# SCH_GD32_KB.net
KiCad netlist of a schematic drawn in EasyEDA
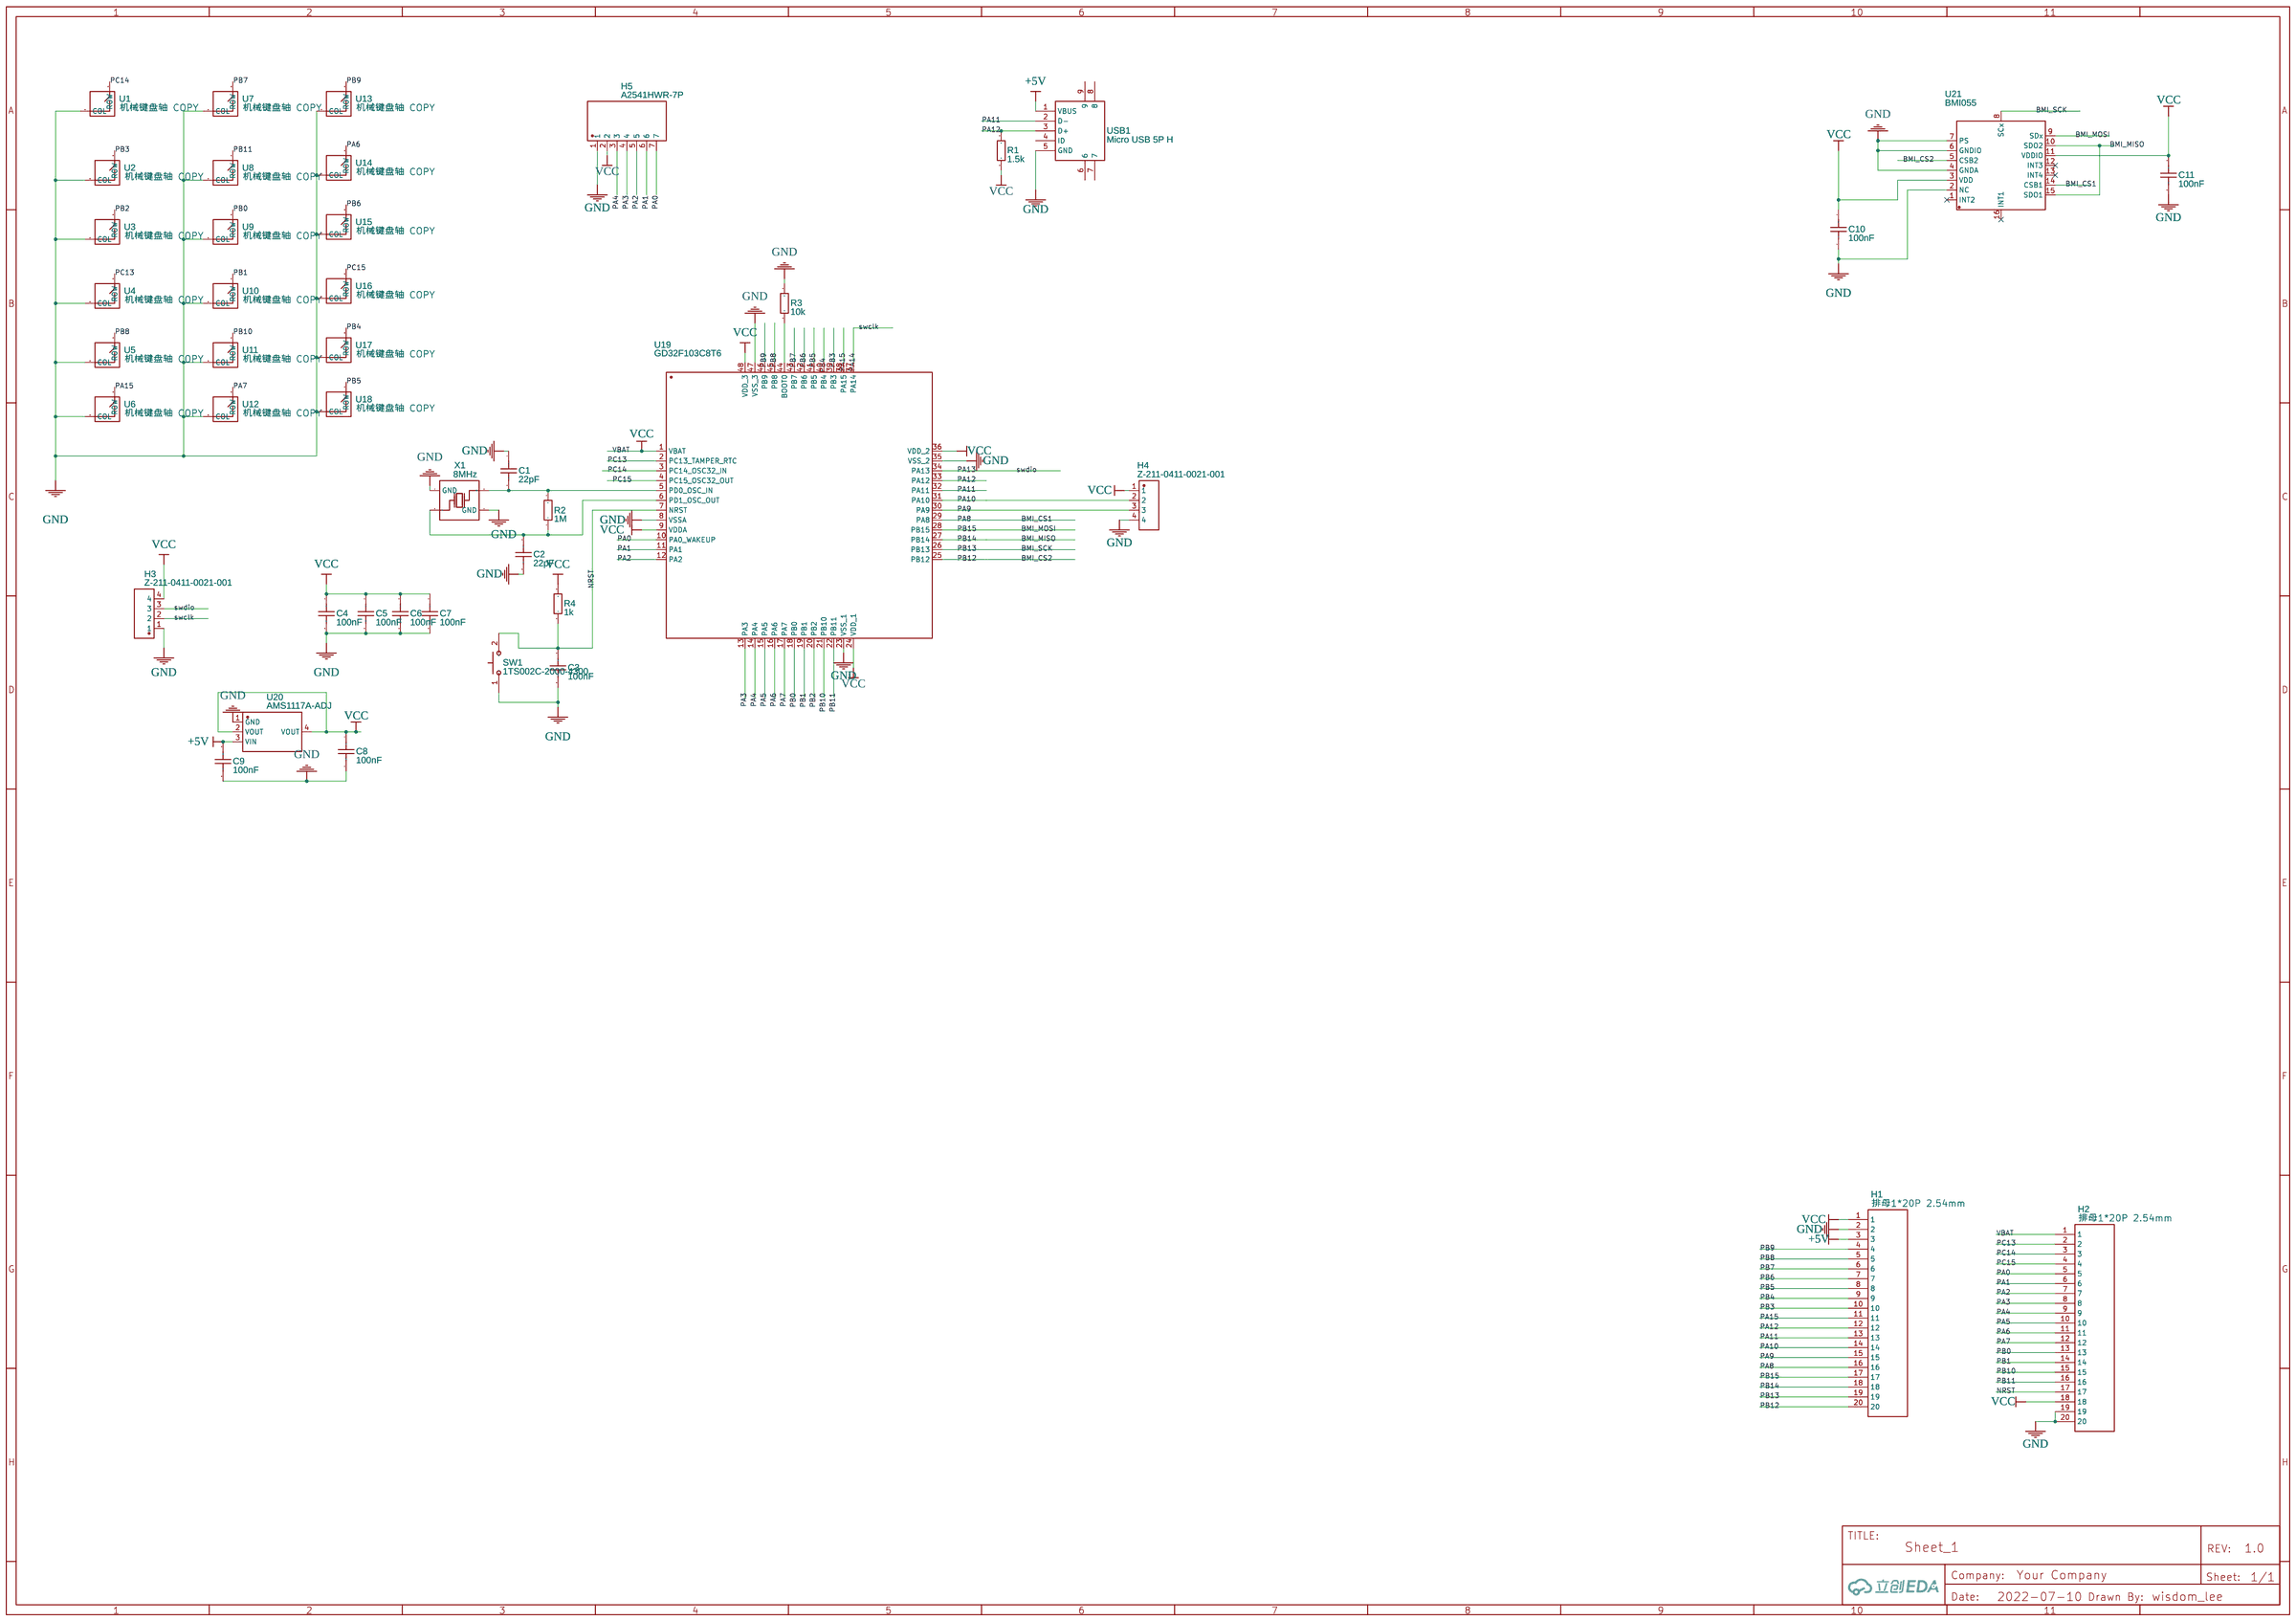
[diagram p0: schematic sheet]

(export (version "E")
  (design (tool "Eeschema 10.0.6"))
  (components
    (comp (ref "C1")
      (value "22pF")
      (fields
        (field (name "BOM_Manufacturer Part") "CC0805KRX7R8BB223")
        (field (name "BOM_Supplier Part") "C327278")
      )
      (libsource (lib "") (part "CC0805KRX7R8BB223"))
    )
    (comp (ref "C2")
      (value "22pF")
      (fields
        (field (name "BOM_Manufacturer Part") "CC0805KRX7R8BB223")
        (field (name "BOM_Supplier Part") "C327278")
      )
      (libsource (lib "") (part "CC0805KRX7R8BB223"))
    )
    (comp (ref "C3")
      (value "100nF")
      (fields
        (field (name "BOM_Manufacturer Part") "CC0805KRX7R8BB223")
        (field (name "BOM_Supplier Part") "C327278")
      )
      (libsource (lib "") (part "CC0805KRX7R8BB223"))
    )
    (comp (ref "C4")
      (value "100nF")
      (fields
        (field (name "BOM_Manufacturer Part") "CC0805KRX7R8BB223")
        (field (name "BOM_Supplier Part") "C327278")
      )
      (libsource (lib "") (part "CC0805KRX7R8BB223"))
    )
    (comp (ref "C5")
      (value "100nF")
      (fields
        (field (name "BOM_Manufacturer Part") "CC0805KRX7R8BB223")
        (field (name "BOM_Supplier Part") "C327278")
      )
      (libsource (lib "") (part "CC0805KRX7R8BB223"))
    )
    (comp (ref "C6")
      (value "100nF")
      (fields
        (field (name "BOM_Manufacturer Part") "CC0805KRX7R8BB223")
        (field (name "BOM_Supplier Part") "C327278")
      )
      (libsource (lib "") (part "CC0805KRX7R8BB223"))
    )
    (comp (ref "C7")
      (value "100nF")
      (fields
        (field (name "BOM_Manufacturer Part") "CC0805KRX7R8BB223")
        (field (name "BOM_Supplier Part") "C327278")
      )
      (libsource (lib "") (part "CC0805KRX7R8BB223"))
    )
    (comp (ref "C8")
      (value "100nF")
      (fields
        (field (name "BOM_Manufacturer Part") "CC0805KRX7R8BB223")
        (field (name "BOM_Supplier Part") "C327278")
      )
      (libsource (lib "") (part "CC0805KRX7R8BB223"))
    )
    (comp (ref "C9")
      (value "100nF")
      (fields
        (field (name "BOM_Manufacturer Part") "CC0805KRX7R8BB223")
        (field (name "BOM_Supplier Part") "C327278")
      )
      (libsource (lib "") (part "CC0805KRX7R8BB223"))
    )
    (comp (ref "C10")
      (value "100nF")
      (fields
        (field (name "BOM_Manufacturer Part") "CC0805KRX7R8BB223")
        (field (name "BOM_Supplier Part") "C327278")
      )
      (libsource (lib "") (part "CC0805KRX7R8BB223"))
    )
    (comp (ref "C11")
      (value "100nF")
      (fields
        (field (name "BOM_Manufacturer Part") "CC0805KRX7R8BB223")
        (field (name "BOM_Supplier Part") "C327278")
      )
      (libsource (lib "") (part "CC0805KRX7R8BB223"))
    )
    (comp (ref "H1")
      (value "排母1*20P 2.54mm")
      (fields (field (name "BOM_Supplier Part") "C169819"))
      (libsource (lib "") (part "排母1*20P 2.54mm"))
    )
    (comp (ref "H2")
      (value "排母1*20P 2.54mm")
      (fields (field (name "BOM_Supplier Part") "C169819"))
      (libsource (lib "") (part "排母1*20P 2.54mm"))
    )
    (comp (ref "H3")
      (value "Z-211-0411-0021-001")
      (fields (field (name "BOM_Supplier Part") "C152150"))
      (libsource (lib "") (part "Z-211-0411-0021-001"))
    )
    (comp (ref "H4")
      (value "Z-211-0411-0021-001")
      (fields (field (name "BOM_Supplier Part") "C152150"))
      (libsource (lib "") (part "Z-211-0411-0021-001_1"))
    )
    (comp (ref "H5")
      (value "A2541HWR-7P")
      (fields (field (name "BOM_Supplier Part") "C225515"))
      (libsource (lib "") (part "A2541HWR-7P"))
    )
    (comp (ref "R1")
      (value "1.5k")
      (fields
        (field (name "BOM_Manufacturer Part") "0805W8F3922T5E")
        (field (name "BOM_Supplier Part") "C60005")
      )
      (libsource (lib "") (part "0805W8F3922T5E_C60005"))
    )
    (comp (ref "R2")
      (value "1M")
      (fields
        (field (name "BOM_Manufacturer Part") "0805W8F3922T5E")
        (field (name "BOM_Supplier Part") "C60005")
      )
      (libsource (lib "") (part "0805W8F3922T5E_C60005"))
    )
    (comp (ref "R3")
      (value "10k")
      (fields
        (field (name "BOM_Manufacturer Part") "0805W8F3922T5E")
        (field (name "BOM_Supplier Part") "C60005")
      )
      (libsource (lib "") (part "0805W8F3922T5E_C60005"))
    )
    (comp (ref "R4")
      (value "1k")
      (fields
        (field (name "BOM_Manufacturer Part") "0805W8F3922T5E")
        (field (name "BOM_Supplier Part") "C60005")
      )
      (libsource (lib "") (part "0805W8F3922T5E_C60005"))
    )
    (comp (ref "SW1")
      (value "1TS002C-2000-4300")
      (fields (field (name "BOM_Supplier Part") "C319339"))
      (libsource (lib "") (part "1TS002C-2000-4300"))
    )
    (comp (ref "U1") (value "机械键盘轴 COPY") (libsource (lib "") (part "机械键盘轴 COPY")))
    (comp (ref "U2") (value "机械键盘轴 COPY") (libsource (lib "") (part "机械键盘轴 COPY")))
    (comp (ref "U3") (value "机械键盘轴 COPY") (libsource (lib "") (part "机械键盘轴 COPY")))
    (comp (ref "U4") (value "机械键盘轴 COPY") (libsource (lib "") (part "机械键盘轴 COPY")))
    (comp (ref "U5") (value "机械键盘轴 COPY") (libsource (lib "") (part "机械键盘轴 COPY")))
    (comp (ref "U6") (value "机械键盘轴 COPY") (libsource (lib "") (part "机械键盘轴 COPY")))
    (comp (ref "U7") (value "机械键盘轴 COPY") (libsource (lib "") (part "机械键盘轴 COPY")))
    (comp (ref "U8") (value "机械键盘轴 COPY") (libsource (lib "") (part "机械键盘轴 COPY")))
    (comp (ref "U9") (value "机械键盘轴 COPY") (libsource (lib "") (part "机械键盘轴 COPY")))
    (comp (ref "U10") (value "机械键盘轴 COPY") (libsource (lib "") (part "机械键盘轴 COPY")))
    (comp (ref "U11") (value "机械键盘轴 COPY") (libsource (lib "") (part "机械键盘轴 COPY")))
    (comp (ref "U12") (value "机械键盘轴 COPY") (libsource (lib "") (part "机械键盘轴 COPY")))
    (comp (ref "U13") (value "机械键盘轴 COPY") (libsource (lib "") (part "机械键盘轴 COPY")))
    (comp (ref "U14") (value "机械键盘轴 COPY") (libsource (lib "") (part "机械键盘轴 COPY")))
    (comp (ref "U15") (value "机械键盘轴 COPY") (libsource (lib "") (part "机械键盘轴 COPY")))
    (comp (ref "U16") (value "机械键盘轴 COPY") (libsource (lib "") (part "机械键盘轴 COPY")))
    (comp (ref "U17") (value "机械键盘轴 COPY") (libsource (lib "") (part "机械键盘轴 COPY")))
    (comp (ref "U18") (value "机械键盘轴 COPY") (libsource (lib "") (part "机械键盘轴 COPY")))
    (comp (ref "U19")
      (value "GD32F103C8T6")
      (fields (field (name "BOM_Supplier Part") "C77994"))
      (libsource (lib "") (part "GD32F103C8T6"))
    )
    (comp (ref "U20")
      (value "AMS1117A-ADJ")
      (fields (field (name "BOM_Supplier Part") "C2984864"))
      (libsource (lib "") (part "AMS1117A-ADJ"))
    )
    (comp (ref "U21")
      (value "BMI055")
      (fields (field (name "BOM_Supplier Part") "C189620"))
      (libsource (lib "") (part "BMI055"))
    )
    (comp (ref "USB1")
      (value "Micro USB 5P H")
      (fields (field (name "BOM_Supplier Part") "C40946"))
      (libsource (lib "") (part "Micro USB 5P H"))
    )
    (comp (ref "X1")
      (value "8MHz")
      (fields
        (field (name "BOM_Manufacturer Part") "7M1204LCSC-EIE4S")
        (field (name "BOM_Supplier Part") "C93114")
      )
      (libsource (lib "") (part "7M1204LCSC-EIE4S"))
    )
  )
  (nets
    (net (code "1") (name "+5V") (class "Default")
      (node (ref "C9") (pin "1") (pinfunction "1_1") (pintype "unspecified"))
      (node (ref "H1") (pin "3") (pinfunction "3_3") (pintype "unspecified"))
      (node (ref "U20") (pin "3") (pinfunction "VIN_3") (pintype "unspecified"))
      (node (ref "USB1") (pin "1") (pinfunction "VBUS_1") (pintype "unspecified"))
    )
    (net (code "2") (name "/BMI_CS1") (class "Default")
      (node (ref "H1") (pin "16") (pinfunction "16_16") (pintype "unspecified"))
      (node (ref "U19") (pin "29") (pinfunction "PA8_29") (pintype "unspecified"))
      (node (ref "U21") (pin "14") (pinfunction "CSB1_14") (pintype "unspecified"))
    )
    (net (code "3") (name "/BMI_CS2") (class "Default")
      (node (ref "H1") (pin "20") (pinfunction "20_20") (pintype "unspecified"))
      (node (ref "U19") (pin "25") (pinfunction "PB12_25") (pintype "unspecified"))
      (node (ref "U21") (pin "5") (pinfunction "CSB2_5") (pintype "unspecified"))
    )
    (net (code "4") (name "/BMI_MISO") (class "Default")
      (node (ref "H1") (pin "18") (pinfunction "18_18") (pintype "unspecified"))
      (node (ref "U19") (pin "27") (pinfunction "PB14_27") (pintype "unspecified"))
      (node (ref "U21") (pin "10") (pinfunction "SDO2_10") (pintype "unspecified"))
      (node (ref "U21") (pin "15") (pinfunction "SDO1_15") (pintype "unspecified"))
    )
    (net (code "5") (name "/BMI_MOSI") (class "Default")
      (node (ref "H1") (pin "17") (pinfunction "17_17") (pintype "unspecified"))
      (node (ref "U19") (pin "28") (pinfunction "PB15_28") (pintype "unspecified"))
      (node (ref "U21") (pin "9") (pinfunction "SDx_9") (pintype "unspecified"))
    )
    (net (code "6") (name "/BMI_SCK") (class "Default")
      (node (ref "H1") (pin "19") (pinfunction "19_19") (pintype "unspecified"))
      (node (ref "U19") (pin "26") (pinfunction "PB13_26") (pintype "unspecified"))
      (node (ref "U21") (pin "8") (pinfunction "SCx_8") (pintype "unspecified"))
    )
    (net (code "7") (name "/NRST") (class "Default")
      (node (ref "C3") (pin "1") (pinfunction "1_1") (pintype "unspecified"))
      (node (ref "H2") (pin "17") (pinfunction "17_17") (pintype "unspecified"))
      (node (ref "R4") (pin "1") (pinfunction "1_1") (pintype "unspecified"))
      (node (ref "SW1") (pin "2") (pinfunction "B_2") (pintype "unspecified"))
      (node (ref "U19") (pin "7") (pinfunction "NRST_7") (pintype "unspecified"))
    )
    (net (code "8") (name "/PA0") (class "Default")
      (node (ref "H2") (pin "5") (pinfunction "5_5") (pintype "unspecified"))
      (node (ref "H5") (pin "7") (pinfunction "7_7") (pintype "unspecified"))
      (node (ref "U19") (pin "10") (pinfunction "PA0_WAKEUP_10") (pintype "unspecified"))
    )
    (net (code "9") (name "/PA1") (class "Default")
      (node (ref "H2") (pin "6") (pinfunction "6_6") (pintype "unspecified"))
      (node (ref "H5") (pin "6") (pinfunction "6_6") (pintype "unspecified"))
      (node (ref "U19") (pin "11") (pinfunction "PA1_11") (pintype "unspecified"))
    )
    (net (code "10") (name "/PA2") (class "Default")
      (node (ref "H2") (pin "7") (pinfunction "7_7") (pintype "unspecified"))
      (node (ref "H5") (pin "5") (pinfunction "5_5") (pintype "unspecified"))
      (node (ref "U19") (pin "12") (pinfunction "PA2_12") (pintype "unspecified"))
    )
    (net (code "11") (name "/PA3") (class "Default")
      (node (ref "H2") (pin "8") (pinfunction "8_8") (pintype "unspecified"))
      (node (ref "H5") (pin "4") (pinfunction "4_4") (pintype "unspecified"))
      (node (ref "U19") (pin "13") (pinfunction "PA3_13") (pintype "unspecified"))
    )
    (net (code "12") (name "/PA4") (class "Default")
      (node (ref "H2") (pin "9") (pinfunction "9_9") (pintype "unspecified"))
      (node (ref "H5") (pin "3") (pinfunction "3_3") (pintype "unspecified"))
      (node (ref "U19") (pin "14") (pinfunction "PA4_14") (pintype "unspecified"))
    )
    (net (code "13") (name "/PA5") (class "Default")
      (node (ref "H2") (pin "10") (pinfunction "10_10") (pintype "unspecified"))
      (node (ref "U19") (pin "15") (pinfunction "PA5_15") (pintype "unspecified"))
    )
    (net (code "14") (name "/PA6") (class "Default")
      (node (ref "H2") (pin "11") (pinfunction "11_11") (pintype "unspecified"))
      (node (ref "U14") (pin "ROW") (pinfunction "ROW_ROW") (pintype "unspecified"))
      (node (ref "U19") (pin "16") (pinfunction "PA6_16") (pintype "unspecified"))
    )
    (net (code "15") (name "/PA7") (class "Default")
      (node (ref "H2") (pin "12") (pinfunction "12_12") (pintype "unspecified"))
      (node (ref "U12") (pin "ROW") (pinfunction "ROW_ROW") (pintype "unspecified"))
      (node (ref "U19") (pin "17") (pinfunction "PA7_17") (pintype "unspecified"))
    )
    (net (code "16") (name "/PA9") (class "Default")
      (node (ref "H1") (pin "15") (pinfunction "15_15") (pintype "unspecified"))
      (node (ref "H4") (pin "3") (pinfunction "3_3") (pintype "unspecified"))
      (node (ref "U19") (pin "30") (pinfunction "PA9_30") (pintype "unspecified"))
    )
    (net (code "17") (name "/PA10") (class "Default")
      (node (ref "H1") (pin "14") (pinfunction "14_14") (pintype "unspecified"))
      (node (ref "H4") (pin "2") (pinfunction "2_2") (pintype "unspecified"))
      (node (ref "U19") (pin "31") (pinfunction "PA10_31") (pintype "unspecified"))
    )
    (net (code "18") (name "/PA11") (class "Default")
      (node (ref "H1") (pin "13") (pinfunction "13_13") (pintype "unspecified"))
      (node (ref "U19") (pin "32") (pinfunction "PA11_32") (pintype "unspecified"))
      (node (ref "USB1") (pin "2") (pinfunction "D-_2") (pintype "unspecified"))
    )
    (net (code "19") (name "/PA12") (class "Default")
      (node (ref "H1") (pin "12") (pinfunction "12_12") (pintype "unspecified"))
      (node (ref "R1") (pin "2") (pinfunction "2_2") (pintype "unspecified"))
      (node (ref "U19") (pin "33") (pinfunction "PA12_33") (pintype "unspecified"))
      (node (ref "USB1") (pin "3") (pinfunction "D+_3") (pintype "unspecified"))
    )
    (net (code "20") (name "/PA13") (class "Default")
      (node (ref "H3") (pin "3") (pinfunction "3_3") (pintype "unspecified"))
      (node (ref "U19") (pin "34") (pinfunction "PA13_34") (pintype "unspecified"))
    )
    (net (code "21") (name "/PA14") (class "Default")
      (node (ref "H3") (pin "2") (pinfunction "2_2") (pintype "unspecified"))
      (node (ref "U19") (pin "37") (pinfunction "PA14_37") (pintype "unspecified"))
    )
    (net (code "22") (name "/PA15") (class "Default")
      (node (ref "H1") (pin "11") (pinfunction "11_11") (pintype "unspecified"))
      (node (ref "U19") (pin "38") (pinfunction "PA15_38") (pintype "unspecified"))
      (node (ref "U6") (pin "ROW") (pinfunction "ROW_ROW") (pintype "unspecified"))
    )
    (net (code "23") (name "/PB0") (class "Default")
      (node (ref "H2") (pin "13") (pinfunction "13_13") (pintype "unspecified"))
      (node (ref "U19") (pin "18") (pinfunction "PB0_18") (pintype "unspecified"))
      (node (ref "U9") (pin "ROW") (pinfunction "ROW_ROW") (pintype "unspecified"))
    )
    (net (code "24") (name "/PB1") (class "Default")
      (node (ref "H2") (pin "14") (pinfunction "14_14") (pintype "unspecified"))
      (node (ref "U10") (pin "ROW") (pinfunction "ROW_ROW") (pintype "unspecified"))
      (node (ref "U19") (pin "19") (pinfunction "PB1_19") (pintype "unspecified"))
    )
    (net (code "25") (name "/PB2") (class "Default")
      (node (ref "U19") (pin "20") (pinfunction "PB2_20") (pintype "unspecified"))
      (node (ref "U3") (pin "ROW") (pinfunction "ROW_ROW") (pintype "unspecified"))
    )
    (net (code "26") (name "/PB3") (class "Default")
      (node (ref "H1") (pin "10") (pinfunction "10_10") (pintype "unspecified"))
      (node (ref "U19") (pin "39") (pinfunction "PB3_39") (pintype "unspecified"))
      (node (ref "U2") (pin "ROW") (pinfunction "ROW_ROW") (pintype "unspecified"))
    )
    (net (code "27") (name "/PB4") (class "Default")
      (node (ref "H1") (pin "9") (pinfunction "9_9") (pintype "unspecified"))
      (node (ref "U17") (pin "ROW") (pinfunction "ROW_ROW") (pintype "unspecified"))
      (node (ref "U19") (pin "40") (pinfunction "PB4_40") (pintype "unspecified"))
    )
    (net (code "28") (name "/PB5") (class "Default")
      (node (ref "H1") (pin "8") (pinfunction "8_8") (pintype "unspecified"))
      (node (ref "U18") (pin "ROW") (pinfunction "ROW_ROW") (pintype "unspecified"))
      (node (ref "U19") (pin "41") (pinfunction "PB5_41") (pintype "unspecified"))
    )
    (net (code "29") (name "/PB6") (class "Default")
      (node (ref "H1") (pin "7") (pinfunction "7_7") (pintype "unspecified"))
      (node (ref "U15") (pin "ROW") (pinfunction "ROW_ROW") (pintype "unspecified"))
      (node (ref "U19") (pin "42") (pinfunction "PB6_42") (pintype "unspecified"))
    )
    (net (code "30") (name "/PB7") (class "Default")
      (node (ref "H1") (pin "6") (pinfunction "6_6") (pintype "unspecified"))
      (node (ref "U19") (pin "43") (pinfunction "PB7_43") (pintype "unspecified"))
      (node (ref "U7") (pin "ROW") (pinfunction "ROW_ROW") (pintype "unspecified"))
    )
    (net (code "31") (name "/PB8") (class "Default")
      (node (ref "H1") (pin "5") (pinfunction "5_5") (pintype "unspecified"))
      (node (ref "U19") (pin "45") (pinfunction "PB8_45") (pintype "unspecified"))
      (node (ref "U5") (pin "ROW") (pinfunction "ROW_ROW") (pintype "unspecified"))
    )
    (net (code "32") (name "/PB9") (class "Default")
      (node (ref "H1") (pin "4") (pinfunction "4_4") (pintype "unspecified"))
      (node (ref "U13") (pin "ROW") (pinfunction "ROW_ROW") (pintype "unspecified"))
      (node (ref "U19") (pin "46") (pinfunction "PB9_46") (pintype "unspecified"))
    )
    (net (code "33") (name "/PB10") (class "Default")
      (node (ref "H2") (pin "15") (pinfunction "15_15") (pintype "unspecified"))
      (node (ref "U11") (pin "ROW") (pinfunction "ROW_ROW") (pintype "unspecified"))
      (node (ref "U19") (pin "21") (pinfunction "PB10_21") (pintype "unspecified"))
    )
    (net (code "34") (name "/PB11") (class "Default")
      (node (ref "H2") (pin "16") (pinfunction "16_16") (pintype "unspecified"))
      (node (ref "U19") (pin "22") (pinfunction "PB11_22") (pintype "unspecified"))
      (node (ref "U8") (pin "ROW") (pinfunction "ROW_ROW") (pintype "unspecified"))
    )
    (net (code "35") (name "/PC13") (class "Default")
      (node (ref "H2") (pin "2") (pinfunction "2_2") (pintype "unspecified"))
      (node (ref "U19") (pin "2") (pinfunction "PC13_TAMPER_RTC_2") (pintype "unspecified"))
      (node (ref "U4") (pin "ROW") (pinfunction "ROW_ROW") (pintype "unspecified"))
    )
    (net (code "36") (name "/PC14") (class "Default")
      (node (ref "H2") (pin "3") (pinfunction "3_3") (pintype "unspecified"))
      (node (ref "U1") (pin "ROW") (pinfunction "ROW_ROW") (pintype "unspecified"))
      (node (ref "U19") (pin "3") (pinfunction "PC14_OSC32_IN_3") (pintype "unspecified"))
    )
    (net (code "37") (name "/PC15") (class "Default")
      (node (ref "H2") (pin "4") (pinfunction "4_4") (pintype "unspecified"))
      (node (ref "U16") (pin "ROW") (pinfunction "ROW_ROW") (pintype "unspecified"))
      (node (ref "U19") (pin "4") (pinfunction "PC15_OSC32_OUT_4") (pintype "unspecified"))
    )
    (net (code "38") (name "GND") (class "Default")
      (node (ref "C1") (pin "1") (pinfunction "1_1") (pintype "unspecified"))
      (node (ref "C10") (pin "2") (pinfunction "2_2") (pintype "unspecified"))
      (node (ref "C11") (pin "2") (pinfunction "2_2") (pintype "unspecified"))
      (node (ref "C2") (pin "2") (pinfunction "2_2") (pintype "unspecified"))
      (node (ref "C3") (pin "2") (pinfunction "2_2") (pintype "unspecified"))
      (node (ref "C4") (pin "2") (pinfunction "2_2") (pintype "unspecified"))
      (node (ref "C5") (pin "2") (pinfunction "2_2") (pintype "unspecified"))
      (node (ref "C6") (pin "2") (pinfunction "2_2") (pintype "unspecified"))
      (node (ref "C7") (pin "2") (pinfunction "2_2") (pintype "unspecified"))
      (node (ref "C8") (pin "2") (pinfunction "2_2") (pintype "unspecified"))
      (node (ref "C9") (pin "2") (pinfunction "2_2") (pintype "unspecified"))
      (node (ref "H1") (pin "2") (pinfunction "2_2") (pintype "unspecified"))
      (node (ref "H2") (pin "19") (pinfunction "19_19") (pintype "unspecified"))
      (node (ref "H2") (pin "20") (pinfunction "20_20") (pintype "unspecified"))
      (node (ref "H3") (pin "1") (pinfunction "1_1") (pintype "unspecified"))
      (node (ref "H4") (pin "4") (pinfunction "4_4") (pintype "unspecified"))
      (node (ref "H5") (pin "1") (pinfunction "1_1") (pintype "unspecified"))
      (node (ref "R3") (pin "2") (pinfunction "2_2") (pintype "unspecified"))
      (node (ref "SW1") (pin "1") (pinfunction "A_1") (pintype "unspecified"))
      (node (ref "U1") (pin "COL") (pinfunction "COL_COL") (pintype "unspecified"))
      (node (ref "U10") (pin "COL") (pinfunction "COL_COL") (pintype "unspecified"))
      (node (ref "U11") (pin "COL") (pinfunction "COL_COL") (pintype "unspecified"))
      (node (ref "U12") (pin "COL") (pinfunction "COL_COL") (pintype "unspecified"))
      (node (ref "U13") (pin "COL") (pinfunction "COL_COL") (pintype "unspecified"))
      (node (ref "U14") (pin "COL") (pinfunction "COL_COL") (pintype "unspecified"))
      (node (ref "U15") (pin "COL") (pinfunction "COL_COL") (pintype "unspecified"))
      (node (ref "U16") (pin "COL") (pinfunction "COL_COL") (pintype "unspecified"))
      (node (ref "U17") (pin "COL") (pinfunction "COL_COL") (pintype "unspecified"))
      (node (ref "U18") (pin "COL") (pinfunction "COL_COL") (pintype "unspecified"))
      (node (ref "U19") (pin "23") (pinfunction "VSS_1_23") (pintype "unspecified"))
      (node (ref "U19") (pin "35") (pinfunction "VSS_2_35") (pintype "unspecified"))
      (node (ref "U19") (pin "47") (pinfunction "VSS_3_47") (pintype "unspecified"))
      (node (ref "U19") (pin "8") (pinfunction "VSSA_8") (pintype "unspecified"))
      (node (ref "U2") (pin "COL") (pinfunction "COL_COL") (pintype "unspecified"))
      (node (ref "U20") (pin "1") (pinfunction "GND_1") (pintype "unspecified"))
      (node (ref "U21") (pin "2") (pinfunction "NC_2") (pintype "unspecified"))
      (node (ref "U21") (pin "4") (pinfunction "GNDA_4") (pintype "unspecified"))
      (node (ref "U21") (pin "6") (pinfunction "GNDIO_6") (pintype "unspecified"))
      (node (ref "U21") (pin "7") (pinfunction "PS_7") (pintype "unspecified"))
      (node (ref "U3") (pin "COL") (pinfunction "COL_COL") (pintype "unspecified"))
      (node (ref "U4") (pin "COL") (pinfunction "COL_COL") (pintype "unspecified"))
      (node (ref "U5") (pin "COL") (pinfunction "COL_COL") (pintype "unspecified"))
      (node (ref "U6") (pin "COL") (pinfunction "COL_COL") (pintype "unspecified"))
      (node (ref "U7") (pin "COL") (pinfunction "COL_COL") (pintype "unspecified"))
      (node (ref "U8") (pin "COL") (pinfunction "COL_COL") (pintype "unspecified"))
      (node (ref "U9") (pin "COL") (pinfunction "COL_COL") (pintype "unspecified"))
      (node (ref "USB1") (pin "5") (pinfunction "GND_5") (pintype "unspecified"))
      (node (ref "X1") (pin "2") (pinfunction "GND_2") (pintype "input"))
      (node (ref "X1") (pin "4") (pinfunction "GND_4") (pintype "input"))
    )
    (net (code "39") (name "Net-(U19-BOOT0)") (class "Default")
      (node (ref "R3") (pin "1") (pinfunction "1_1") (pintype "unspecified"))
      (node (ref "U19") (pin "44") (pinfunction "BOOT0_44") (pintype "unspecified"))
    )
    (net (code "40") (name "Net-(U19-PD0_OSC_IN)") (class "Default")
      (node (ref "C1") (pin "2") (pinfunction "2_2") (pintype "unspecified"))
      (node (ref "R2") (pin "2") (pinfunction "2_2") (pintype "unspecified"))
      (node (ref "U19") (pin "5") (pinfunction "PD0_OSC_IN_5") (pintype "unspecified"))
      (node (ref "X1") (pin "3") (pinfunction "OSC2_3") (pintype "input"))
    )
    (net (code "41") (name "Net-(U19-PD1_OSC_OUT)") (class "Default")
      (node (ref "C2") (pin "1") (pinfunction "1_1") (pintype "unspecified"))
      (node (ref "R2") (pin "1") (pinfunction "1_1") (pintype "unspecified"))
      (node (ref "U19") (pin "6") (pinfunction "PD1_OSC_OUT_6") (pintype "unspecified"))
      (node (ref "X1") (pin "1") (pinfunction "OSC1_1") (pintype "input"))
    )
    (net (code "42") (name "VCC") (class "Default")
      (node (ref "C10") (pin "1") (pinfunction "1_1") (pintype "unspecified"))
      (node (ref "C11") (pin "1") (pinfunction "1_1") (pintype "unspecified"))
      (node (ref "C4") (pin "1") (pinfunction "1_1") (pintype "unspecified"))
      (node (ref "C5") (pin "1") (pinfunction "1_1") (pintype "unspecified"))
      (node (ref "C6") (pin "1") (pinfunction "1_1") (pintype "unspecified"))
      (node (ref "C7") (pin "1") (pinfunction "1_1") (pintype "unspecified"))
      (node (ref "C8") (pin "1") (pinfunction "1_1") (pintype "unspecified"))
      (node (ref "H1") (pin "1") (pinfunction "1_1") (pintype "unspecified"))
      (node (ref "H2") (pin "1") (pinfunction "1_1") (pintype "unspecified"))
      (node (ref "H2") (pin "18") (pinfunction "18_18") (pintype "unspecified"))
      (node (ref "H3") (pin "4") (pinfunction "4_4") (pintype "unspecified"))
      (node (ref "H4") (pin "1") (pinfunction "1_1") (pintype "unspecified"))
      (node (ref "H5") (pin "2") (pinfunction "2_2") (pintype "unspecified"))
      (node (ref "R1") (pin "1") (pinfunction "1_1") (pintype "unspecified"))
      (node (ref "R4") (pin "2") (pinfunction "2_2") (pintype "unspecified"))
      (node (ref "U19") (pin "1") (pinfunction "VBAT_1") (pintype "unspecified"))
      (node (ref "U19") (pin "24") (pinfunction "VDD_1_24") (pintype "unspecified"))
      (node (ref "U19") (pin "36") (pinfunction "VDD_2_36") (pintype "unspecified"))
      (node (ref "U19") (pin "48") (pinfunction "VDD_3_48") (pintype "unspecified"))
      (node (ref "U19") (pin "9") (pinfunction "VDDA_9") (pintype "unspecified"))
      (node (ref "U20") (pin "2") (pinfunction "VOUT_2") (pintype "unspecified"))
      (node (ref "U20") (pin "4") (pinfunction "VOUT_4") (pintype "unspecified"))
      (node (ref "U21") (pin "11") (pinfunction "VDDIO_11") (pintype "unspecified"))
      (node (ref "U21") (pin "3") (pinfunction "VDD_3") (pintype "unspecified"))
    )
    (net (code "43") (name "unconnected-(U21-INT1-Pad16)") (class "Default")
      (node (ref "U21") (pin "16") (pinfunction "INT1_16") (pintype "unspecified+no_connect"))
    )
    (net (code "44") (name "unconnected-(U21-INT2-Pad1)") (class "Default")
      (node (ref "U21") (pin "1") (pinfunction "INT2_1") (pintype "unspecified+no_connect"))
    )
    (net (code "45") (name "unconnected-(U21-INT3-Pad12)") (class "Default")
      (node (ref "U21") (pin "12") (pinfunction "INT3_12") (pintype "unspecified+no_connect"))
    )
    (net (code "46") (name "unconnected-(U21-INT4-Pad13)") (class "Default")
      (node (ref "U21") (pin "13") (pinfunction "INT4_13") (pintype "unspecified+no_connect"))
    )
    (net (code "47") (name "unconnected-(USB1-ID-Pad4)") (class "Default")
      (node (ref "USB1") (pin "4") (pinfunction "ID_4") (pintype "unspecified"))
    )
    (net (code "48") (name "unconnected-(USB1-Pad6)") (class "Default")
      (node (ref "USB1") (pin "6") (pinfunction "6_6") (pintype "unspecified"))
    )
    (net (code "49") (name "unconnected-(USB1-Pad7)") (class "Default")
      (node (ref "USB1") (pin "7") (pinfunction "7_7") (pintype "unspecified"))
    )
    (net (code "50") (name "unconnected-(USB1-Pad8)") (class "Default")
      (node (ref "USB1") (pin "8") (pinfunction "8_8") (pintype "unspecified"))
    )
    (net (code "51") (name "unconnected-(USB1-Pad9)") (class "Default")
      (node (ref "USB1") (pin "9") (pinfunction "9_9") (pintype "unspecified"))
    )
  )
)
